# Connectors.net
KiCad netlist of a schematic drawn in Altium Designer
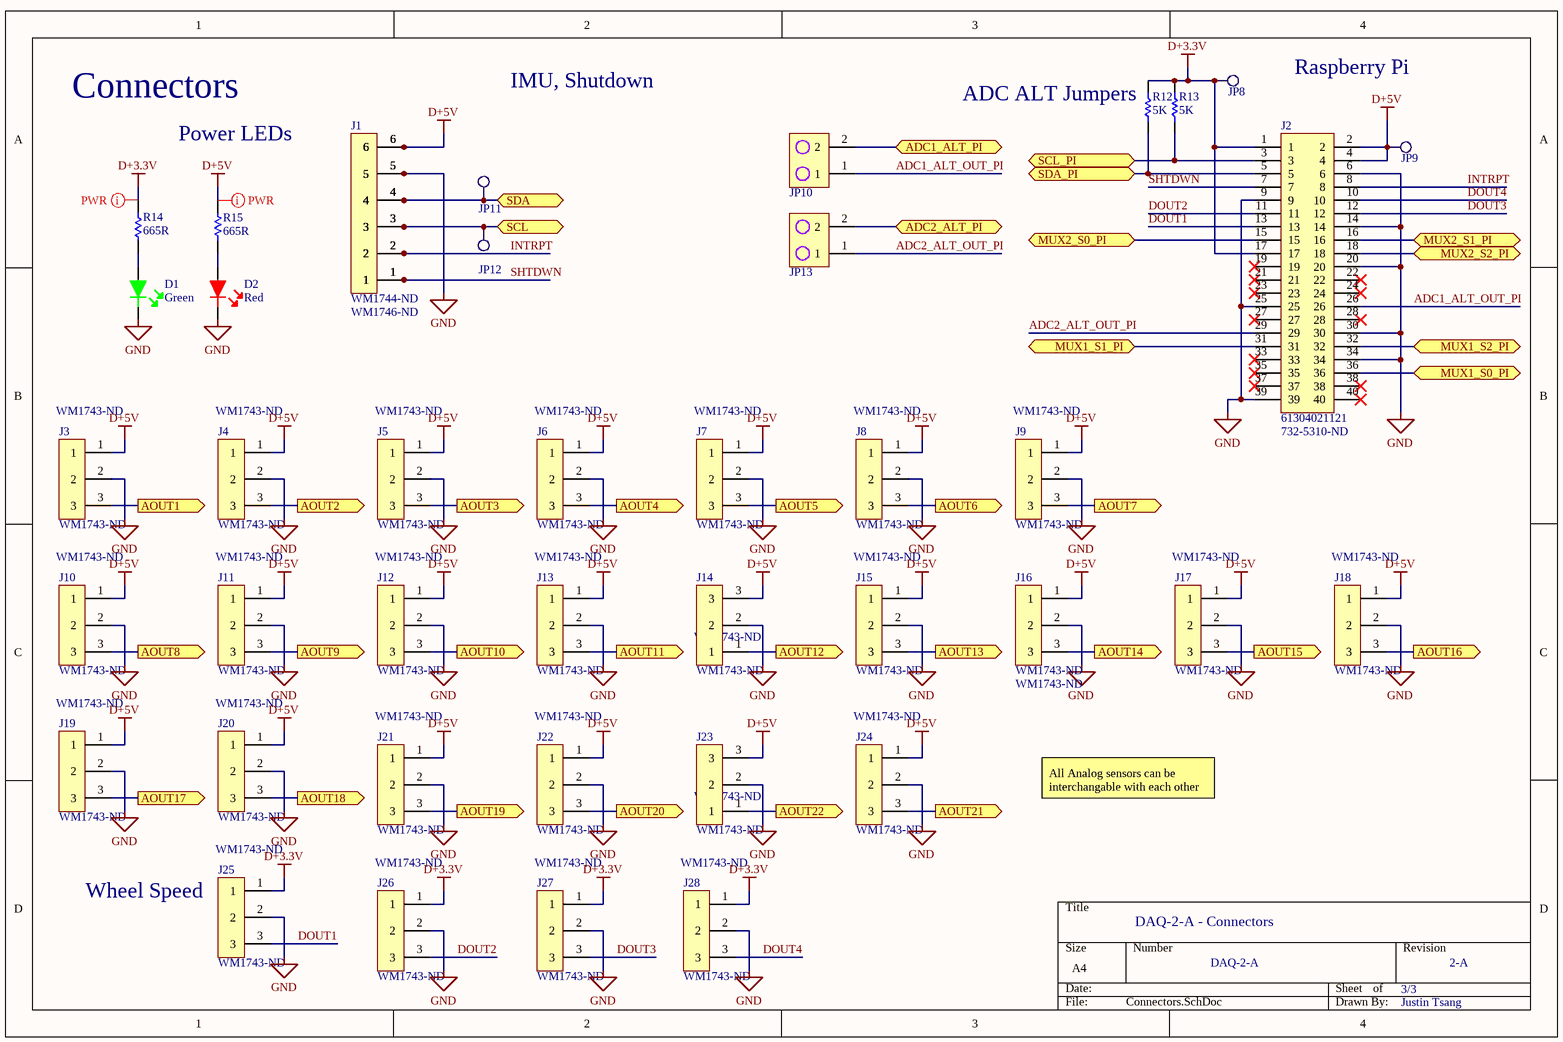
[diagram p0: Connectors.SchDoc]

(export (version "E")
  (design (tool "Eeschema 10.0.6"))
  (components
    (comp (ref "D1")
      (value "Green")
      (footprint "LED-0603")
      (description "LED GREEN CLEAR 0603 SMD")
      (fields
        (field (name "MANUFACTURER") "Wurth Electronics")
        (field (name "MANUFACTURER PART NUMBER") "150060VS75000")
      )
      (libsource (lib "LEDs") (part "LED-Green"))
    )
    (comp (ref "D2")
      (value "Red")
      (footprint "LED-0603")
      (description "LED RED CLEAR 0603 SMD")
      (fields
        (field (name "MANUFACTURER") "Wurth Electronics")
        (field (name "MANUFACTURER PART NUMBER") "150060RS75000")
      )
      (libsource (lib "LEDs") (part "LED-Red"))
    )
    (comp (ref "J1")
      (value "WM1744-ND")
      (footprint "1X6_1.25MM")
      (description "CONN HEADER R/A 6POS 1.25MM")
      (fields (field (name "SUPPLIER PART NUMBER 1") "WM1746-ND"))
      (libsource (lib "New_Parts") (part "CONN_1X6_1.25MM"))
    )
    (comp (ref "J2")
      (value "61304021121")
      (footprint "2x40_Header")
      (description "CONN HEADER VERT 40POS 2.54MM")
      (fields (field (name "SUPPLIER PART NUMBER 1") "732-5310-ND"))
      (libsource (lib "New_Parts") (part "CONN_2X40"))
    )
    (comp (ref "J3")
      (value "WM1743-ND")
      (footprint "1X3_1.25MM")
      (description "CONN HEADER R/A 3POS 1.25MM")
      (fields (field (name "SUPPLIER PART NUMBER 1") "WM1743-ND"))
      (libsource (lib "New_Parts") (part "CONN_1X3_1.25MM"))
    )
    (comp (ref "J4")
      (value "WM1743-ND")
      (footprint "1X3_1.25MM")
      (description "CONN HEADER R/A 3POS 1.25MM")
      (fields (field (name "SUPPLIER PART NUMBER 1") "WM1743-ND"))
      (libsource (lib "New_Parts") (part "CONN_1X3_1.25MM"))
    )
    (comp (ref "J5")
      (value "WM1743-ND")
      (footprint "1X3_1.25MM")
      (description "CONN HEADER R/A 3POS 1.25MM")
      (fields (field (name "SUPPLIER PART NUMBER 1") "WM1743-ND"))
      (libsource (lib "New_Parts") (part "CONN_1X3_1.25MM"))
    )
    (comp (ref "J6")
      (value "WM1743-ND")
      (footprint "1X3_1.25MM")
      (description "CONN HEADER R/A 3POS 1.25MM")
      (fields (field (name "SUPPLIER PART NUMBER 1") "WM1743-ND"))
      (libsource (lib "New_Parts") (part "CONN_1X3_1.25MM"))
    )
    (comp (ref "J7")
      (value "WM1743-ND")
      (footprint "1X3_1.25MM")
      (description "CONN HEADER R/A 3POS 1.25MM")
      (fields (field (name "SUPPLIER PART NUMBER 1") "WM1743-ND"))
      (libsource (lib "New_Parts") (part "CONN_1X3_1.25MM"))
    )
    (comp (ref "J8")
      (value "WM1743-ND")
      (footprint "1X3_1.25MM")
      (description "CONN HEADER R/A 3POS 1.25MM")
      (fields (field (name "SUPPLIER PART NUMBER 1") "WM1743-ND"))
      (libsource (lib "New_Parts") (part "CONN_1X3_1.25MM"))
    )
    (comp (ref "J9")
      (value "WM1743-ND")
      (footprint "1X3_1.25MM")
      (description "CONN HEADER R/A 3POS 1.25MM")
      (fields (field (name "SUPPLIER PART NUMBER 1") "WM1743-ND"))
      (libsource (lib "New_Parts") (part "CONN_1X3_1.25MM"))
    )
    (comp (ref "J10")
      (value "WM1743-ND")
      (footprint "1X3_1.25MM")
      (description "CONN HEADER R/A 3POS 1.25MM")
      (fields (field (name "SUPPLIER PART NUMBER 1") "WM1743-ND"))
      (libsource (lib "New_Parts") (part "CONN_1X3_1.25MM"))
    )
    (comp (ref "J11")
      (value "WM1743-ND")
      (footprint "1X3_1.25MM")
      (description "CONN HEADER R/A 3POS 1.25MM")
      (fields (field (name "SUPPLIER PART NUMBER 1") "WM1743-ND"))
      (libsource (lib "New_Parts") (part "CONN_1X3_1.25MM"))
    )
    (comp (ref "J12")
      (value "WM1743-ND")
      (footprint "1X3_1.25MM")
      (description "CONN HEADER R/A 3POS 1.25MM")
      (fields (field (name "SUPPLIER PART NUMBER 1") "WM1743-ND"))
      (libsource (lib "New_Parts") (part "CONN_1X3_1.25MM"))
    )
    (comp (ref "J13")
      (value "WM1743-ND")
      (footprint "1X3_1.25MM")
      (description "CONN HEADER R/A 3POS 1.25MM")
      (fields (field (name "SUPPLIER PART NUMBER 1") "WM1743-ND"))
      (libsource (lib "New_Parts") (part "CONN_1X3_1.25MM"))
    )
    (comp (ref "J14")
      (value "WM1743-ND")
      (footprint "1X3_1.25MM")
      (description "CONN HEADER R/A 3POS 1.25MM")
      (fields (field (name "SUPPLIER PART NUMBER 1") "WM1743-ND"))
      (libsource (lib "") (part "CONN_1X3_1.25MM_1"))
    )
    (comp (ref "J15")
      (value "WM1743-ND")
      (footprint "1X3_1.25MM")
      (description "CONN HEADER R/A 3POS 1.25MM")
      (fields (field (name "SUPPLIER PART NUMBER 1") "WM1743-ND"))
      (libsource (lib "New_Parts") (part "CONN_1X3_1.25MM"))
    )
    (comp (ref "J16")
      (value "WM1743-ND")
      (footprint "1X3_1.25MM")
      (description "CONN HEADER R/A 3POS 1.25MM")
      (fields (field (name "SUPPLIER PART NUMBER 1") "WM1743-ND"))
      (libsource (lib "New_Parts") (part "CONN_1X3_1.25MM"))
    )
    (comp (ref "J17")
      (value "WM1743-ND")
      (footprint "1X3_1.25MM")
      (description "CONN HEADER R/A 3POS 1.25MM")
      (fields (field (name "SUPPLIER PART NUMBER 1") "WM1743-ND"))
      (libsource (lib "New_Parts") (part "CONN_1X3_1.25MM"))
    )
    (comp (ref "J18")
      (value "WM1743-ND")
      (footprint "1X3_1.25MM")
      (description "CONN HEADER R/A 3POS 1.25MM")
      (fields (field (name "SUPPLIER PART NUMBER 1") "WM1743-ND"))
      (libsource (lib "New_Parts") (part "CONN_1X3_1.25MM"))
    )
    (comp (ref "J19")
      (value "WM1743-ND")
      (footprint "1X3_1.25MM")
      (description "CONN HEADER R/A 3POS 1.25MM")
      (fields (field (name "SUPPLIER PART NUMBER 1") "WM1743-ND"))
      (libsource (lib "New_Parts") (part "CONN_1X3_1.25MM"))
    )
    (comp (ref "J20")
      (value "WM1743-ND")
      (footprint "1X3_1.25MM")
      (description "CONN HEADER R/A 3POS 1.25MM")
      (fields (field (name "SUPPLIER PART NUMBER 1") "WM1743-ND"))
      (libsource (lib "New_Parts") (part "CONN_1X3_1.25MM"))
    )
    (comp (ref "J21")
      (value "WM1743-ND")
      (footprint "1X3_1.25MM")
      (description "CONN HEADER R/A 3POS 1.25MM")
      (fields (field (name "SUPPLIER PART NUMBER 1") "WM1743-ND"))
      (libsource (lib "New_Parts") (part "CONN_1X3_1.25MM"))
    )
    (comp (ref "J22")
      (value "WM1743-ND")
      (footprint "1X3_1.25MM")
      (description "CONN HEADER R/A 3POS 1.25MM")
      (fields (field (name "SUPPLIER PART NUMBER 1") "WM1743-ND"))
      (libsource (lib "New_Parts") (part "CONN_1X3_1.25MM"))
    )
    (comp (ref "J23")
      (value "WM1743-ND")
      (footprint "1X3_1.25MM")
      (description "CONN HEADER R/A 3POS 1.25MM")
      (fields (field (name "SUPPLIER PART NUMBER 1") "WM1743-ND"))
      (libsource (lib "") (part "CONN_1X3_1.25MM_1"))
    )
    (comp (ref "J24")
      (value "WM1743-ND")
      (footprint "1X3_1.25MM")
      (description "CONN HEADER R/A 3POS 1.25MM")
      (fields (field (name "SUPPLIER PART NUMBER 1") "WM1743-ND"))
      (libsource (lib "New_Parts") (part "CONN_1X3_1.25MM"))
    )
    (comp (ref "J25")
      (value "WM1743-ND")
      (footprint "1X3_1.25MM")
      (description "CONN HEADER R/A 3POS 1.25MM")
      (fields (field (name "SUPPLIER PART NUMBER 1") "WM1743-ND"))
      (libsource (lib "New_Parts") (part "CONN_1X3_1.25MM"))
    )
    (comp (ref "J26")
      (value "WM1743-ND")
      (footprint "1X3_1.25MM")
      (description "CONN HEADER R/A 3POS 1.25MM")
      (fields (field (name "SUPPLIER PART NUMBER 1") "WM1743-ND"))
      (libsource (lib "New_Parts") (part "CONN_1X3_1.25MM"))
    )
    (comp (ref "J27")
      (value "WM1743-ND")
      (footprint "1X3_1.25MM")
      (description "CONN HEADER R/A 3POS 1.25MM")
      (fields (field (name "SUPPLIER PART NUMBER 1") "WM1743-ND"))
      (libsource (lib "New_Parts") (part "CONN_1X3_1.25MM"))
    )
    (comp (ref "J28")
      (value "WM1743-ND")
      (footprint "1X3_1.25MM")
      (description "CONN HEADER R/A 3POS 1.25MM")
      (fields (field (name "SUPPLIER PART NUMBER 1") "WM1743-ND"))
      (libsource (lib "New_Parts") (part "CONN_1X3_1.25MM"))
    )
    (comp (ref "JP8")
      (value "Testpoint2")
      (footprint "TP2")
      (description "Single layer pad TP")
      (libsource (lib "Misc") (part "Testpoint2"))
    )
    (comp (ref "JP9")
      (value "Testpoint2")
      (footprint "TP2")
      (description "Single layer pad TP")
      (libsource (lib "Misc") (part "Testpoint2"))
    )
    (comp (ref "JP10")
      (value "732-5315-ND")
      (footprint "2PIN-JP")
      (description "CONN HEADER VERT 2POS 2.54MM")
      (libsource (lib "Connectors") (part "2PIN-TEST"))
    )
    (comp (ref "JP11")
      (value "Testpoint2")
      (footprint "TP2")
      (description "Single layer pad TP")
      (libsource (lib "Misc") (part "Testpoint2"))
    )
    (comp (ref "JP12")
      (value "Testpoint2")
      (footprint "TP2")
      (description "Single layer pad TP")
      (libsource (lib "Misc") (part "Testpoint2"))
    )
    (comp (ref "JP13")
      (value "732-5315-ND")
      (footprint "2PIN-JP")
      (description "CONN HEADER VERT 2POS 2.54MM")
      (libsource (lib "Connectors") (part "2PIN-TEST"))
    )
    (comp (ref "R12")
      (value "5K")
      (footprint "RES-0603")
      (description "RES SMD 4.99K OHM 1% 1/10W 0603")
      (fields
        (field (name "MANUFACTURER") "Bourns")
        (field (name "MANUFACTURER PART NUMBER") "CR0603-FX-4991ELF")
      )
      (libsource (lib "Resistors") (part "0603-5KR"))
    )
    (comp (ref "R13")
      (value "5K")
      (footprint "RES-0603")
      (description "RES SMD 4.99K OHM 1% 1/10W 0603")
      (fields
        (field (name "MANUFACTURER") "Bourns")
        (field (name "MANUFACTURER PART NUMBER") "CR0603-FX-4991ELF")
      )
      (libsource (lib "Resistors") (part "0603-5KR"))
    )
    (comp (ref "R14")
      (value "665R")
      (footprint "RES-0603")
      (description "RES SMD 665 OHM 1% 1/10W 0603")
      (fields
        (field (name "MANUFACTURER") "Yageo")
        (field (name "MANUFACTURER PART NUMBER") "RC0603FR-07665RL")
      )
      (libsource (lib "Resistors") (part "0603-665R"))
    )
    (comp (ref "R15")
      (value "665R")
      (footprint "RES-0603")
      (description "RES SMD 665 OHM 1% 1/10W 0603")
      (fields
        (field (name "MANUFACTURER") "Yageo")
        (field (name "MANUFACTURER PART NUMBER") "RC0603FR-07665RL")
      )
      (libsource (lib "Resistors") (part "0603-665R"))
    )
  )
  (nets
    (net (code "1") (name "/ADC1_ALT_OUT_PI") (class "Default")
      (node (ref "J2") (pin "26") (pinfunction "26_26") (pintype "passive"))
      (node (ref "JP10") (pin "1") (pinfunction "1_1") (pintype "passive"))
    )
    (net (code "2") (name "/ADC1_ALT_PI") (class "Default")
      (node (ref "JP10") (pin "2") (pinfunction "2_2") (pintype "passive"))
    )
    (net (code "3") (name "/ADC2_ALT_OUT_PI") (class "Default")
      (node (ref "J2") (pin "29") (pinfunction "29_29") (pintype "passive"))
      (node (ref "JP13") (pin "1") (pinfunction "1_1") (pintype "passive"))
    )
    (net (code "4") (name "/ADC2_ALT_PI") (class "Default")
      (node (ref "JP13") (pin "2") (pinfunction "2_2") (pintype "passive"))
    )
    (net (code "5") (name "/AOUT1") (class "Default")
      (node (ref "J3") (pin "3") (pinfunction "3_3") (pintype "passive"))
    )
    (net (code "6") (name "/AOUT2") (class "Default")
      (node (ref "J4") (pin "3") (pinfunction "3_3") (pintype "passive"))
    )
    (net (code "7") (name "/AOUT3") (class "Default")
      (node (ref "J5") (pin "3") (pinfunction "3_3") (pintype "passive"))
    )
    (net (code "8") (name "/AOUT4") (class "Default")
      (node (ref "J6") (pin "3") (pinfunction "3_3") (pintype "passive"))
    )
    (net (code "9") (name "/AOUT5") (class "Default")
      (node (ref "J7") (pin "3") (pinfunction "3_3") (pintype "passive"))
    )
    (net (code "10") (name "/AOUT6") (class "Default")
      (node (ref "J8") (pin "3") (pinfunction "3_3") (pintype "passive"))
    )
    (net (code "11") (name "/AOUT7") (class "Default")
      (node (ref "J9") (pin "3") (pinfunction "3_3") (pintype "passive"))
    )
    (net (code "12") (name "/AOUT8") (class "Default")
      (node (ref "J10") (pin "3") (pinfunction "3_3") (pintype "passive"))
    )
    (net (code "13") (name "/AOUT9") (class "Default")
      (node (ref "J11") (pin "3") (pinfunction "3_3") (pintype "passive"))
    )
    (net (code "14") (name "/AOUT10") (class "Default")
      (node (ref "J12") (pin "3") (pinfunction "3_3") (pintype "passive"))
    )
    (net (code "15") (name "/AOUT11") (class "Default")
      (node (ref "J13") (pin "3") (pinfunction "3_3") (pintype "passive"))
    )
    (net (code "16") (name "/AOUT12") (class "Default")
      (node (ref "J14") (pin "1") (pinfunction "1_1") (pintype "passive"))
    )
    (net (code "17") (name "/AOUT13") (class "Default")
      (node (ref "J15") (pin "3") (pinfunction "3_3") (pintype "passive"))
    )
    (net (code "18") (name "/AOUT14") (class "Default")
      (node (ref "J16") (pin "3") (pinfunction "3_3") (pintype "passive"))
    )
    (net (code "19") (name "/AOUT15") (class "Default")
      (node (ref "J17") (pin "3") (pinfunction "3_3") (pintype "passive"))
    )
    (net (code "20") (name "/AOUT16") (class "Default")
      (node (ref "J18") (pin "3") (pinfunction "3_3") (pintype "passive"))
    )
    (net (code "21") (name "/AOUT17") (class "Default")
      (node (ref "J19") (pin "3") (pinfunction "3_3") (pintype "passive"))
    )
    (net (code "22") (name "/AOUT18") (class "Default")
      (node (ref "J20") (pin "3") (pinfunction "3_3") (pintype "passive"))
    )
    (net (code "23") (name "/AOUT19") (class "Default")
      (node (ref "J21") (pin "3") (pinfunction "3_3") (pintype "passive"))
    )
    (net (code "24") (name "/AOUT20") (class "Default")
      (node (ref "J22") (pin "3") (pinfunction "3_3") (pintype "passive"))
    )
    (net (code "25") (name "/AOUT21") (class "Default")
      (node (ref "J24") (pin "3") (pinfunction "3_3") (pintype "passive"))
    )
    (net (code "26") (name "/AOUT22") (class "Default")
      (node (ref "J23") (pin "1") (pinfunction "1_1") (pintype "passive"))
    )
    (net (code "27") (name "/DOUT1") (class "Default")
      (node (ref "J2") (pin "13") (pinfunction "13_13") (pintype "passive"))
      (node (ref "J25") (pin "3") (pinfunction "3_3") (pintype "passive"))
    )
    (net (code "28") (name "/DOUT2") (class "Default")
      (node (ref "J2") (pin "11") (pinfunction "11_11") (pintype "passive"))
      (node (ref "J26") (pin "3") (pinfunction "3_3") (pintype "passive"))
    )
    (net (code "29") (name "/DOUT3") (class "Default")
      (node (ref "J2") (pin "12") (pinfunction "12_12") (pintype "passive"))
      (node (ref "J27") (pin "3") (pinfunction "3_3") (pintype "passive"))
    )
    (net (code "30") (name "/DOUT4") (class "Default")
      (node (ref "J2") (pin "10") (pinfunction "10_10") (pintype "passive"))
      (node (ref "J28") (pin "3") (pinfunction "3_3") (pintype "passive"))
    )
    (net (code "31") (name "/INTRPT") (class "Default")
      (node (ref "J1") (pin "2") (pinfunction "2_2") (pintype "passive"))
      (node (ref "J2") (pin "8") (pinfunction "8_8") (pintype "passive"))
    )
    (net (code "32") (name "/MUX1_S0_PI") (class "Default")
      (node (ref "J2") (pin "36") (pinfunction "36_36") (pintype "passive"))
    )
    (net (code "33") (name "/MUX1_S1_PI") (class "Default")
      (node (ref "J2") (pin "31") (pinfunction "31_31") (pintype "passive"))
    )
    (net (code "34") (name "/MUX1_S2_PI") (class "Default")
      (node (ref "J2") (pin "32") (pinfunction "32_32") (pintype "passive"))
    )
    (net (code "35") (name "/MUX2_S0_PI") (class "Default")
      (node (ref "J2") (pin "15") (pinfunction "15_15") (pintype "passive"))
    )
    (net (code "36") (name "/MUX2_S1_PI") (class "Default")
      (node (ref "J2") (pin "16") (pinfunction "16_16") (pintype "passive"))
    )
    (net (code "37") (name "/MUX2_S2_PI") (class "Default")
      (node (ref "J2") (pin "18") (pinfunction "18_18") (pintype "passive"))
    )
    (net (code "38") (name "/SCL") (class "Default")
      (node (ref "J1") (pin "3") (pinfunction "3_3") (pintype "passive"))
      (node (ref "JP12") (pin "1") (pinfunction "1_1") (pintype "passive"))
    )
    (net (code "39") (name "/SCL_PI") (class "Default")
      (node (ref "J2") (pin "3") (pinfunction "3_3") (pintype "passive"))
      (node (ref "R13") (pin "1") (pinfunction "1_1") (pintype "passive"))
    )
    (net (code "40") (name "/SDA") (class "Default")
      (node (ref "J1") (pin "4") (pinfunction "4_4") (pintype "passive"))
      (node (ref "JP11") (pin "1") (pinfunction "1_1") (pintype "passive"))
    )
    (net (code "41") (name "/SDA_PI") (class "Default")
      (node (ref "J2") (pin "5") (pinfunction "5_5") (pintype "passive"))
      (node (ref "R12") (pin "1") (pinfunction "1_1") (pintype "passive"))
    )
    (net (code "42") (name "/SHTDWN") (class "Default")
      (node (ref "J1") (pin "1") (pinfunction "1_1") (pintype "passive"))
      (node (ref "J2") (pin "7") (pinfunction "7_7") (pintype "passive"))
    )
    (net (code "43") (name "D+3.3V") (class "Default")
      (node (ref "J2") (pin "1") (pinfunction "1_1") (pintype "passive"))
      (node (ref "J2") (pin "17") (pinfunction "17_17") (pintype "passive"))
      (node (ref "J25") (pin "1") (pinfunction "1_1") (pintype "passive"))
      (node (ref "J26") (pin "1") (pinfunction "1_1") (pintype "passive"))
      (node (ref "J27") (pin "1") (pinfunction "1_1") (pintype "passive"))
      (node (ref "J28") (pin "1") (pinfunction "1_1") (pintype "passive"))
      (node (ref "JP8") (pin "1") (pinfunction "1_1") (pintype "passive"))
      (node (ref "R12") (pin "2") (pinfunction "2_2") (pintype "passive"))
      (node (ref "R13") (pin "2") (pinfunction "2_2") (pintype "passive"))
      (node (ref "R14") (pin "1") (pinfunction "1_1") (pintype "passive"))
    )
    (net (code "44") (name "D+5V") (class "Default")
      (node (ref "J1") (pin "6") (pinfunction "6_6") (pintype "passive"))
      (node (ref "J10") (pin "1") (pinfunction "1_1") (pintype "passive"))
      (node (ref "J11") (pin "1") (pinfunction "1_1") (pintype "passive"))
      (node (ref "J12") (pin "1") (pinfunction "1_1") (pintype "passive"))
      (node (ref "J13") (pin "1") (pinfunction "1_1") (pintype "passive"))
      (node (ref "J14") (pin "3") (pinfunction "3_3") (pintype "passive"))
      (node (ref "J15") (pin "1") (pinfunction "1_1") (pintype "passive"))
      (node (ref "J16") (pin "1") (pinfunction "1_1") (pintype "passive"))
      (node (ref "J17") (pin "1") (pinfunction "1_1") (pintype "passive"))
      (node (ref "J18") (pin "1") (pinfunction "1_1") (pintype "passive"))
      (node (ref "J19") (pin "1") (pinfunction "1_1") (pintype "passive"))
      (node (ref "J2") (pin "2") (pinfunction "2_2") (pintype "passive"))
      (node (ref "J2") (pin "4") (pinfunction "4_4") (pintype "passive"))
      (node (ref "J20") (pin "1") (pinfunction "1_1") (pintype "passive"))
      (node (ref "J21") (pin "1") (pinfunction "1_1") (pintype "passive"))
      (node (ref "J22") (pin "1") (pinfunction "1_1") (pintype "passive"))
      (node (ref "J23") (pin "3") (pinfunction "3_3") (pintype "passive"))
      (node (ref "J24") (pin "1") (pinfunction "1_1") (pintype "passive"))
      (node (ref "J3") (pin "1") (pinfunction "1_1") (pintype "passive"))
      (node (ref "J4") (pin "1") (pinfunction "1_1") (pintype "passive"))
      (node (ref "J5") (pin "1") (pinfunction "1_1") (pintype "passive"))
      (node (ref "J6") (pin "1") (pinfunction "1_1") (pintype "passive"))
      (node (ref "J7") (pin "1") (pinfunction "1_1") (pintype "passive"))
      (node (ref "J8") (pin "1") (pinfunction "1_1") (pintype "passive"))
      (node (ref "J9") (pin "1") (pinfunction "1_1") (pintype "passive"))
      (node (ref "JP9") (pin "1") (pinfunction "1_1") (pintype "passive"))
      (node (ref "R15") (pin "2") (pinfunction "2_2") (pintype "passive"))
    )
    (net (code "45") (name "GND") (class "Default")
      (node (ref "D1") (pin "2") (pinfunction "2_2") (pintype "passive"))
      (node (ref "D2") (pin "2") (pinfunction "2_2") (pintype "passive"))
      (node (ref "J1") (pin "5") (pinfunction "5_5") (pintype "passive"))
      (node (ref "J10") (pin "2") (pinfunction "2_2") (pintype "passive"))
      (node (ref "J11") (pin "2") (pinfunction "2_2") (pintype "passive"))
      (node (ref "J12") (pin "2") (pinfunction "2_2") (pintype "passive"))
      (node (ref "J13") (pin "2") (pinfunction "2_2") (pintype "passive"))
      (node (ref "J14") (pin "2") (pinfunction "2_2") (pintype "passive"))
      (node (ref "J15") (pin "2") (pinfunction "2_2") (pintype "passive"))
      (node (ref "J16") (pin "2") (pinfunction "2_2") (pintype "passive"))
      (node (ref "J17") (pin "2") (pinfunction "2_2") (pintype "passive"))
      (node (ref "J18") (pin "2") (pinfunction "2_2") (pintype "passive"))
      (node (ref "J19") (pin "2") (pinfunction "2_2") (pintype "passive"))
      (node (ref "J2") (pin "14") (pinfunction "14_14") (pintype "passive"))
      (node (ref "J2") (pin "20") (pinfunction "20_20") (pintype "passive"))
      (node (ref "J2") (pin "25") (pinfunction "25_25") (pintype "passive"))
      (node (ref "J2") (pin "30") (pinfunction "30_30") (pintype "passive"))
      (node (ref "J2") (pin "34") (pinfunction "34_34") (pintype "passive"))
      (node (ref "J2") (pin "39") (pinfunction "39_39") (pintype "passive"))
      (node (ref "J2") (pin "6") (pinfunction "6_6") (pintype "passive"))
      (node (ref "J2") (pin "9") (pinfunction "9_9") (pintype "passive"))
      (node (ref "J20") (pin "2") (pinfunction "2_2") (pintype "passive"))
      (node (ref "J21") (pin "2") (pinfunction "2_2") (pintype "passive"))
      (node (ref "J22") (pin "2") (pinfunction "2_2") (pintype "passive"))
      (node (ref "J23") (pin "2") (pinfunction "2_2") (pintype "passive"))
      (node (ref "J24") (pin "2") (pinfunction "2_2") (pintype "passive"))
      (node (ref "J25") (pin "2") (pinfunction "2_2") (pintype "passive"))
      (node (ref "J26") (pin "2") (pinfunction "2_2") (pintype "passive"))
      (node (ref "J27") (pin "2") (pinfunction "2_2") (pintype "passive"))
      (node (ref "J28") (pin "2") (pinfunction "2_2") (pintype "passive"))
      (node (ref "J3") (pin "2") (pinfunction "2_2") (pintype "passive"))
      (node (ref "J4") (pin "2") (pinfunction "2_2") (pintype "passive"))
      (node (ref "J5") (pin "2") (pinfunction "2_2") (pintype "passive"))
      (node (ref "J6") (pin "2") (pinfunction "2_2") (pintype "passive"))
      (node (ref "J7") (pin "2") (pinfunction "2_2") (pintype "passive"))
      (node (ref "J8") (pin "2") (pinfunction "2_2") (pintype "passive"))
      (node (ref "J9") (pin "2") (pinfunction "2_2") (pintype "passive"))
    )
    (net (code "46") (name "Net-(D1-Pad1)") (class "Default")
      (node (ref "D1") (pin "1") (pinfunction "1_1") (pintype "passive"))
      (node (ref "R14") (pin "2") (pinfunction "2_2") (pintype "passive"))
    )
    (net (code "47") (name "Net-(D2-Pad1)") (class "Default")
      (node (ref "D2") (pin "1") (pinfunction "1_1") (pintype "passive"))
      (node (ref "R15") (pin "1") (pinfunction "1_1") (pintype "passive"))
    )
    (net (code "48") (name "unconnected-(J2-Pad19)") (class "Default")
      (node (ref "J2") (pin "19") (pinfunction "19_19") (pintype "passive+no_connect"))
    )
    (net (code "49") (name "unconnected-(J2-Pad21)") (class "Default")
      (node (ref "J2") (pin "21") (pinfunction "21_21") (pintype "passive+no_connect"))
    )
    (net (code "50") (name "unconnected-(J2-Pad22)") (class "Default")
      (node (ref "J2") (pin "22") (pinfunction "22_22") (pintype "passive+no_connect"))
    )
    (net (code "51") (name "unconnected-(J2-Pad23)") (class "Default")
      (node (ref "J2") (pin "23") (pinfunction "23_23") (pintype "passive+no_connect"))
    )
    (net (code "52") (name "unconnected-(J2-Pad24)") (class "Default")
      (node (ref "J2") (pin "24") (pinfunction "24_24") (pintype "passive+no_connect"))
    )
    (net (code "53") (name "unconnected-(J2-Pad27)") (class "Default")
      (node (ref "J2") (pin "27") (pinfunction "27_27") (pintype "passive+no_connect"))
    )
    (net (code "54") (name "unconnected-(J2-Pad28)") (class "Default")
      (node (ref "J2") (pin "28") (pinfunction "28_28") (pintype "passive+no_connect"))
    )
    (net (code "55") (name "unconnected-(J2-Pad33)") (class "Default")
      (node (ref "J2") (pin "33") (pinfunction "33_33") (pintype "passive+no_connect"))
    )
    (net (code "56") (name "unconnected-(J2-Pad35)") (class "Default")
      (node (ref "J2") (pin "35") (pinfunction "35_35") (pintype "passive+no_connect"))
    )
    (net (code "57") (name "unconnected-(J2-Pad37)") (class "Default")
      (node (ref "J2") (pin "37") (pinfunction "37_37") (pintype "passive+no_connect"))
    )
    (net (code "58") (name "unconnected-(J2-Pad38)") (class "Default")
      (node (ref "J2") (pin "38") (pinfunction "38_38") (pintype "passive+no_connect"))
    )
    (net (code "59") (name "unconnected-(J2-Pad40)") (class "Default")
      (node (ref "J2") (pin "40") (pinfunction "40_40") (pintype "passive+no_connect"))
    )
  )
)
